# ridicideskaV2.net
KiCad netlist of a schematic drawn in EAGLE
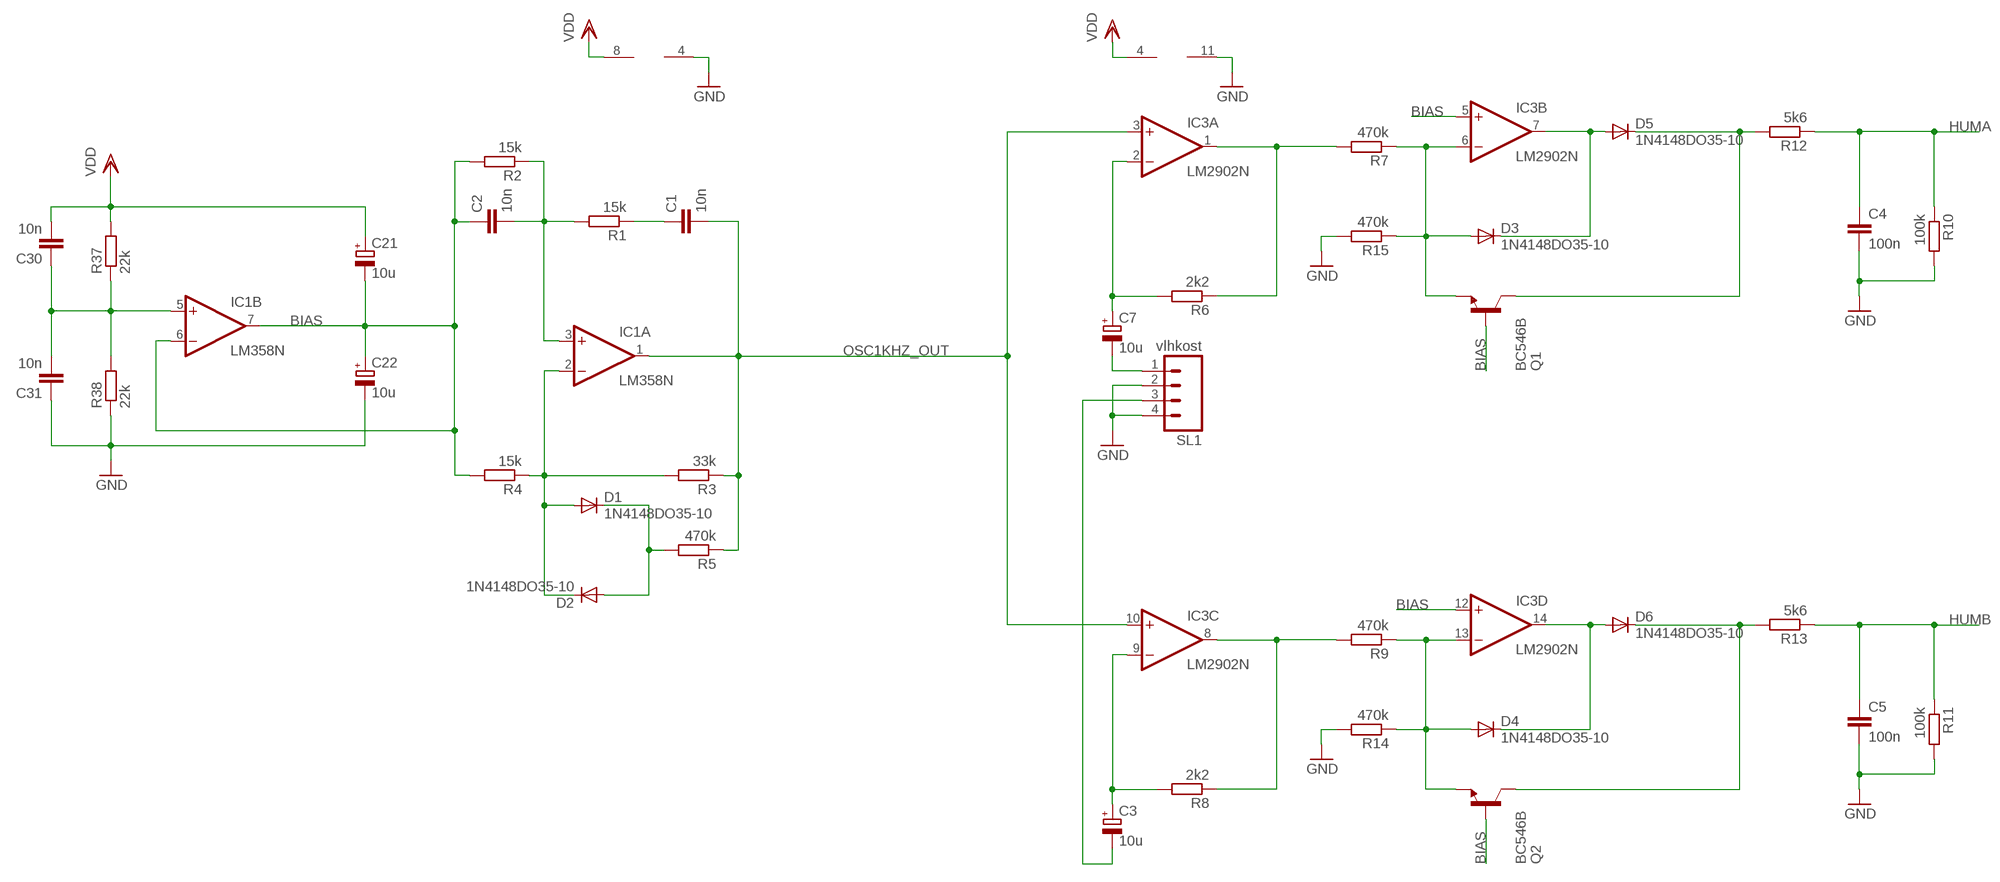
[diagram p0: schematic, sheet 1]
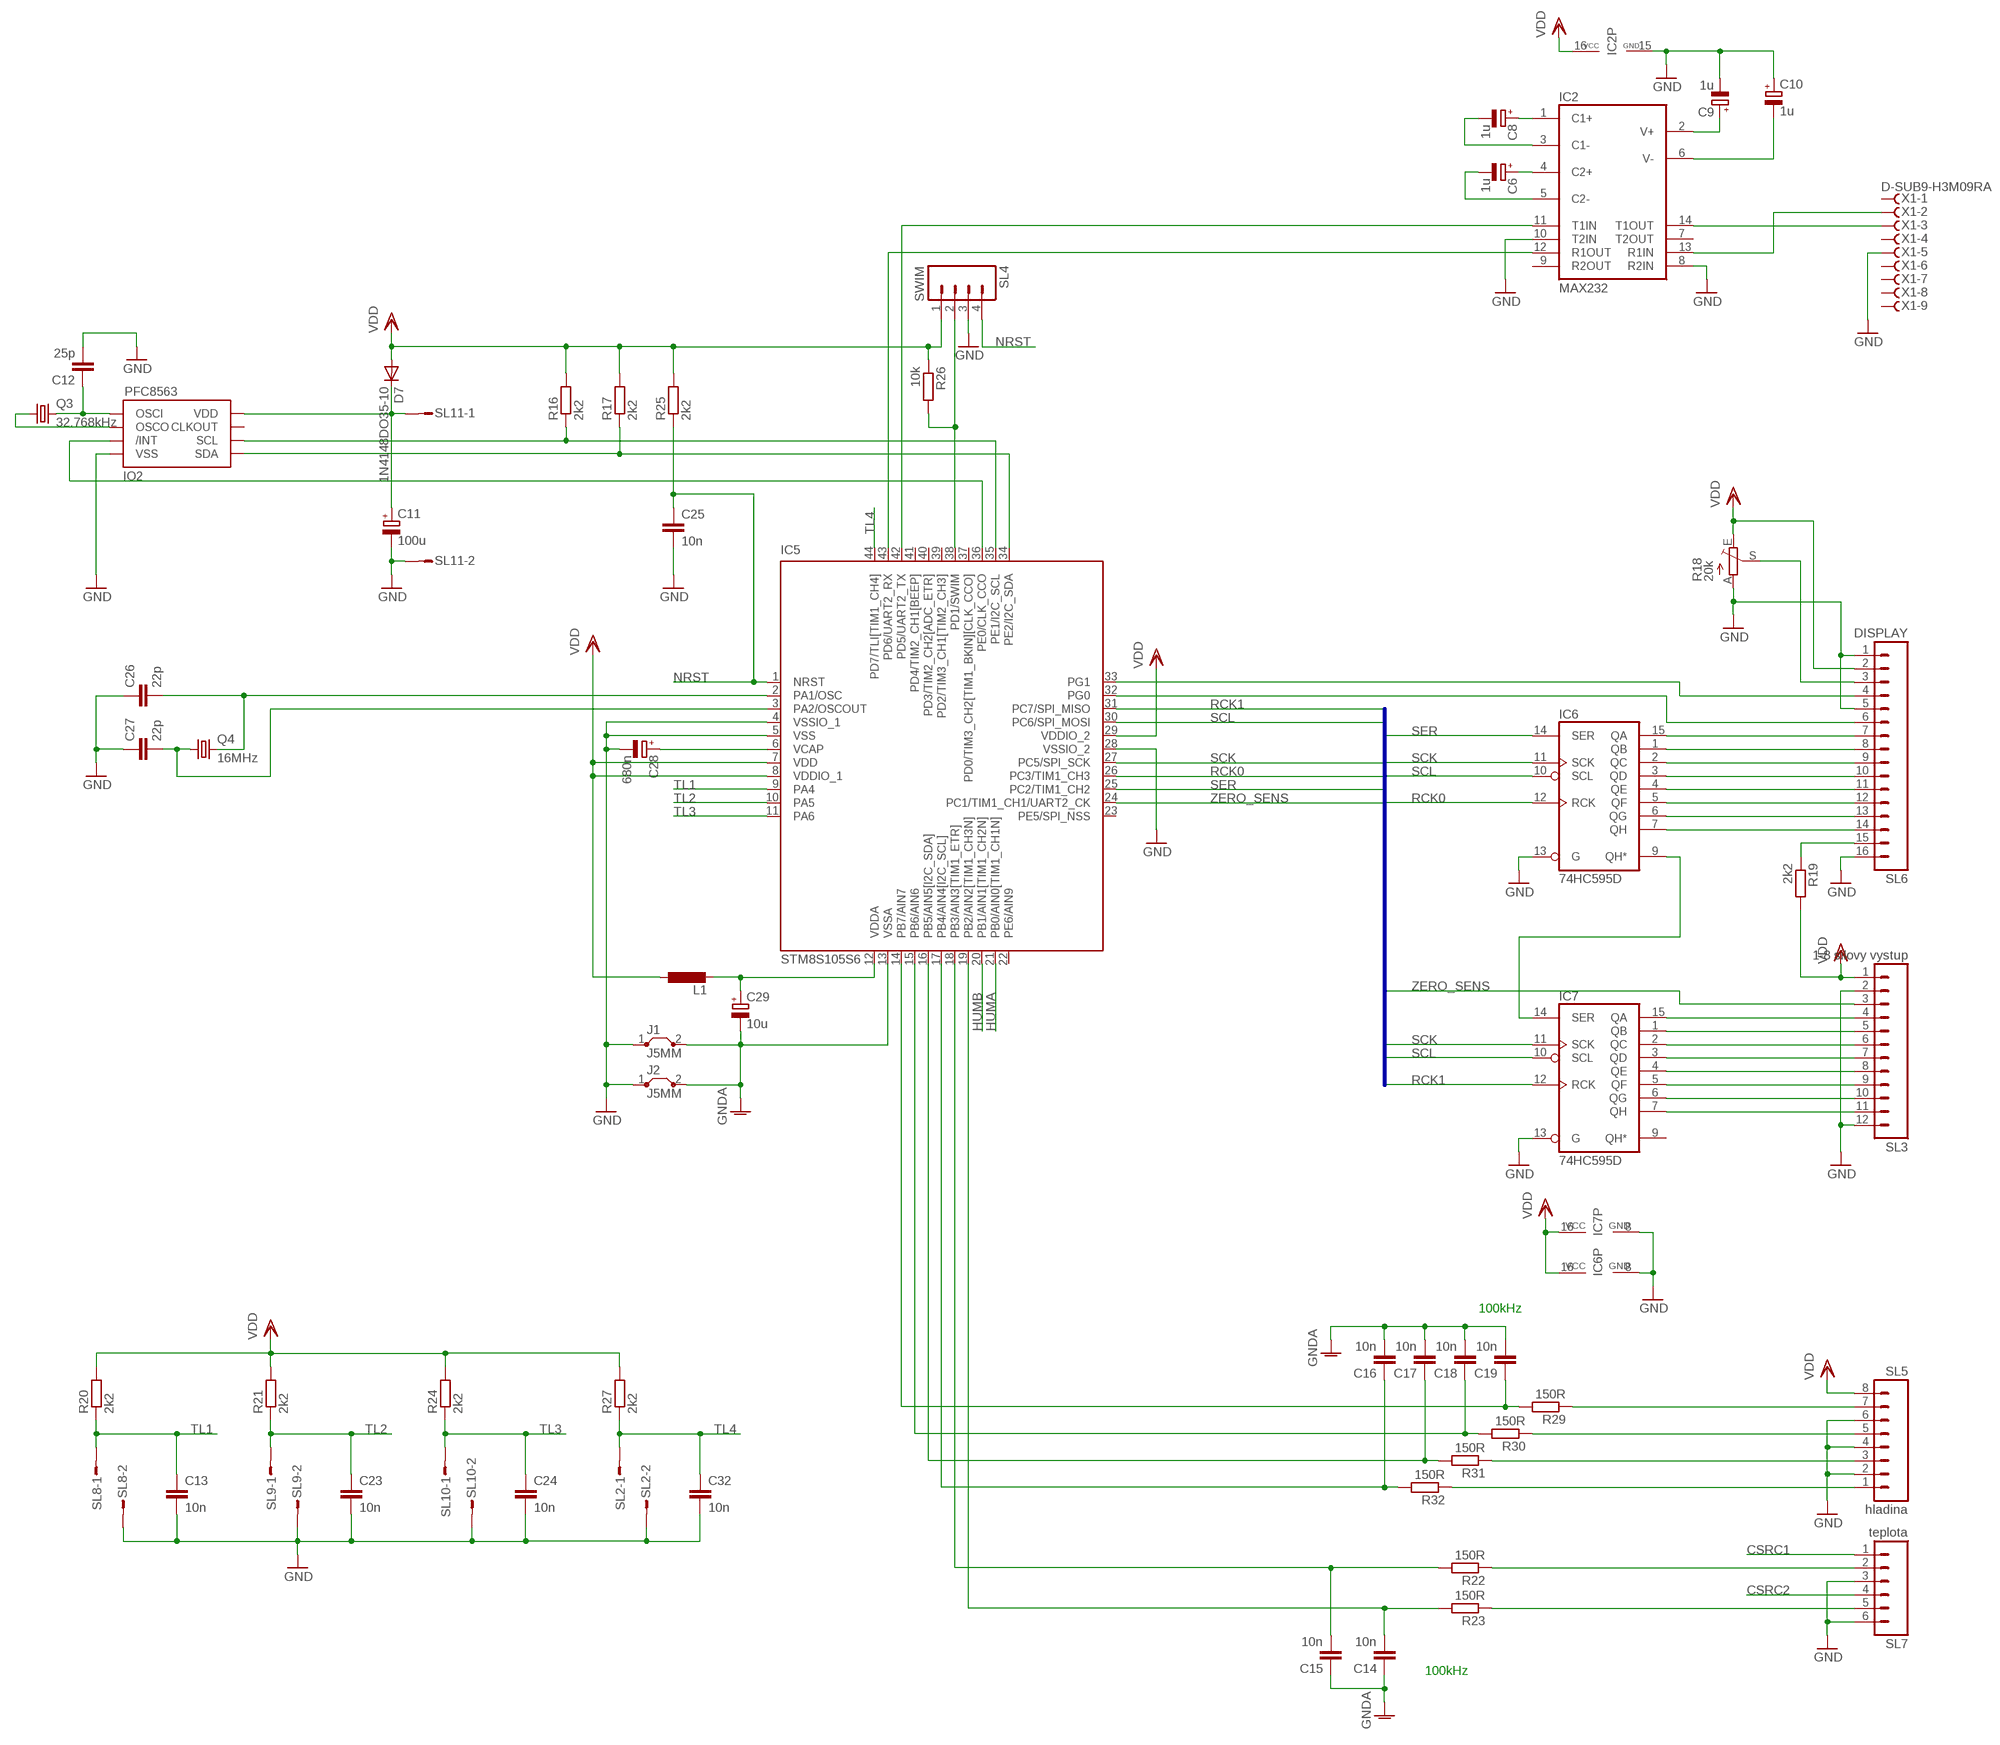
[diagram p1: schematic, sheet 2]
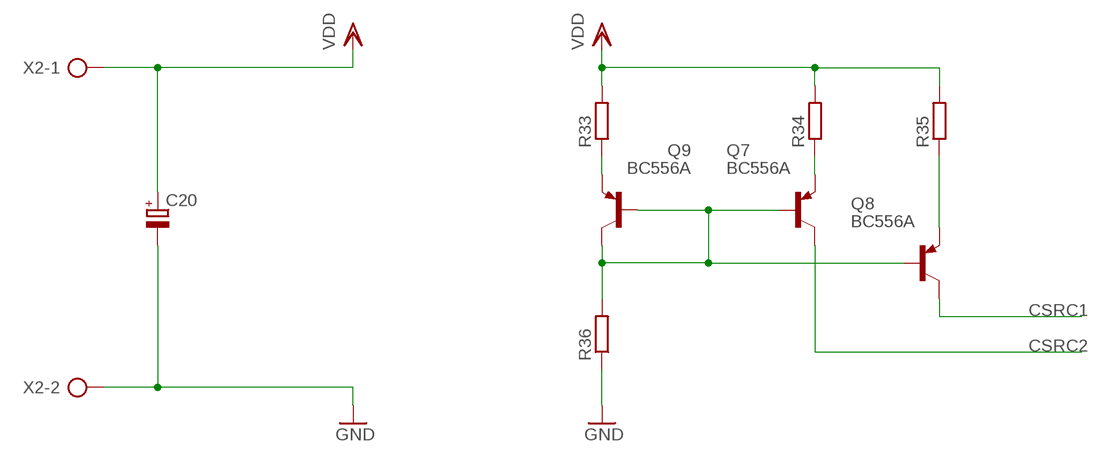
[diagram p2: schematic, sheet 3]

(export (version "E")
  (design (tool "Eeschema 10.0.6"))
  (components
    (comp (ref "C20")
      (value "CPOL-EUE5-10.5")
      (footprint "eagle-import:E5-10,5")
      (libsource (lib "eagle-import") (part "resistor_CPOL-EUE5-10.5"))
    )
    (comp (ref "Q7")
      (value "BC556A")
      (footprint "eagle-import:TO92-EBC")
      (libsource (lib "eagle-import") (part "BC556A"))
    )
    (comp (ref "Q8")
      (value "BC556A")
      (footprint "eagle-import:TO92-EBC")
      (libsource (lib "eagle-import") (part "BC556A"))
    )
    (comp (ref "Q9")
      (value "BC556A")
      (footprint "eagle-import:TO92-EBC")
      (libsource (lib "eagle-import") (part "BC556A"))
    )
    (comp (ref "R33")
      (value "R-EU_R0805")
      (footprint "eagle-import:R0805")
      (libsource (lib "eagle-import") (part "R-EU_R0805"))
    )
    (comp (ref "R34")
      (value "R-EU_R0805")
      (footprint "eagle-import:R0805")
      (libsource (lib "eagle-import") (part "R-EU_R0805"))
    )
    (comp (ref "R35")
      (value "R-EU_R0805")
      (footprint "eagle-import:R0805")
      (libsource (lib "eagle-import") (part "R-EU_R0805"))
    )
    (comp (ref "R36")
      (value "R-EU_R0805")
      (footprint "eagle-import:R0805")
      (libsource (lib "eagle-import") (part "R-EU_R0805"))
    )
    (comp (ref "X2")
      (value "AK300/2")
      (footprint "eagle-import:AK300_2")
      (libsource (lib "eagle-import") (part "AK300/2"))
    )
    (comp (ref "C6")
      (value "1u")
      (footprint "eagle-import:E3,5-8")
      (libsource (lib "eagle-import") (part "resistor_CPOL-EUE3.5-8"))
    )
    (comp (ref "C8")
      (value "1u")
      (footprint "eagle-import:E3,5-8")
      (libsource (lib "eagle-import") (part "resistor_CPOL-EUE3.5-8"))
    )
    (comp (ref "C9")
      (value "1u")
      (footprint "eagle-import:E3,5-8")
      (libsource (lib "eagle-import") (part "resistor_CPOL-EUE3.5-8"))
    )
    (comp (ref "C10")
      (value "1u")
      (footprint "eagle-import:E3,5-8")
      (libsource (lib "eagle-import") (part "resistor_CPOL-EUE3.5-8"))
    )
    (comp (ref "C11")
      (value "100u")
      (footprint "eagle-import:E5-10,5")
      (libsource (lib "eagle-import") (part "resistor_CPOL-EUE5-10.5"))
    )
    (comp (ref "C12")
      (value "25p")
      (footprint "eagle-import:C0805")
      (libsource (lib "eagle-import") (part "C-EUC0805"))
    )
    (comp (ref "C13")
      (value "10n")
      (footprint "eagle-import:C0805")
      (libsource (lib "eagle-import") (part "C-EUC0805"))
    )
    (comp (ref "C14")
      (value "10n")
      (footprint "eagle-import:C0805")
      (libsource (lib "eagle-import") (part "C-EUC0805"))
    )
    (comp (ref "C15")
      (value "10n")
      (footprint "eagle-import:C0805")
      (libsource (lib "eagle-import") (part "C-EUC0805"))
    )
    (comp (ref "C16")
      (value "10n")
      (footprint "eagle-import:C0805")
      (libsource (lib "eagle-import") (part "C-EUC0805"))
    )
    (comp (ref "C17")
      (value "10n")
      (footprint "eagle-import:C0805")
      (libsource (lib "eagle-import") (part "C-EUC0805"))
    )
    (comp (ref "C18")
      (value "10n")
      (footprint "eagle-import:C0805")
      (libsource (lib "eagle-import") (part "C-EUC0805"))
    )
    (comp (ref "C19")
      (value "10n")
      (footprint "eagle-import:C0805")
      (libsource (lib "eagle-import") (part "C-EUC0805"))
    )
    (comp (ref "C23")
      (value "10n")
      (footprint "eagle-import:C0805")
      (libsource (lib "eagle-import") (part "C-EUC0805"))
    )
    (comp (ref "C24")
      (value "10n")
      (footprint "eagle-import:C0805")
      (libsource (lib "eagle-import") (part "C-EUC0805"))
    )
    (comp (ref "C25")
      (value "10n")
      (footprint "eagle-import:C0805")
      (libsource (lib "eagle-import") (part "C-EUC0805"))
    )
    (comp (ref "C26")
      (value "22p")
      (footprint "eagle-import:C0805")
      (libsource (lib "eagle-import") (part "C-EUC0805"))
    )
    (comp (ref "C27")
      (value "22p")
      (footprint "eagle-import:C0805")
      (libsource (lib "eagle-import") (part "C-EUC0805"))
    )
    (comp (ref "C28")
      (value "680n")
      (footprint "eagle-import:SMC_B")
      (libsource (lib "eagle-import") (part "CPOL-EUSMCB"))
    )
    (comp (ref "C29")
      (value "10u")
      (footprint "eagle-import:E5-10,5")
      (libsource (lib "eagle-import") (part "resistor_CPOL-EUE5-10.5"))
    )
    (comp (ref "C32")
      (value "10n")
      (footprint "eagle-import:C0805")
      (libsource (lib "eagle-import") (part "C-EUC0805"))
    )
    (comp (ref "D7")
      (value "1N4148DO35-10")
      (footprint "eagle-import:DO35-10")
      (libsource (lib "eagle-import") (part "1N4148DO35-10"))
    )
    (comp (ref "IC2")
      (value "MAX232")
      (footprint "eagle-import:DIL16")
      (fields (field (name "MF") "MAXIM") (field (name "MPN") "MAX232ACPE+"))
      (libsource (lib "eagle-import") (part "MAX232"))
    )
    (comp (ref "IC5")
      (value "STM8S105S6")
      (footprint "eagle-import:LQFP44-10X10")
      (fields (field (name "MPN") "STM8S105S6T6C"))
      (libsource (lib "eagle-import") (part "STM8S105S6"))
    )
    (comp (ref "IC6")
      (value "74HC595D")
      (footprint "eagle-import:SO16")
      (libsource (lib "eagle-import") (part "74595DHC"))
    )
    (comp (ref "IC7")
      (value "74HC595D")
      (footprint "eagle-import:SO16")
      (libsource (lib "eagle-import") (part "74595DHC"))
    )
    (comp (ref "IO2")
      (value "PFC8563")
      (footprint "eagle-import:SO08")
      (libsource (lib "eagle-import") (part "PFC8563"))
    )
    (comp (ref "J1")
      (value "J5MM")
      (footprint "eagle-import:05")
      (libsource (lib "eagle-import") (part "J5MM"))
    )
    (comp (ref "J2")
      (value "J5MM")
      (footprint "eagle-import:05")
      (libsource (lib "eagle-import") (part "J5MM"))
    )
    (comp (ref "L1")
      (value "L-EU0207/12")
      (footprint "eagle-import:0207_12")
      (libsource (lib "eagle-import") (part "L-EU0207/12"))
    )
    (comp (ref "Q3")
      (value "32.768kHz")
      (footprint "eagle-import:HC49U70")
      (libsource (lib "eagle-import") (part "CRYSTALHC49U70"))
    )
    (comp (ref "Q4")
      (value "16MHz")
      (footprint "eagle-import:HC49U-V")
      (libsource (lib "eagle-import") (part "CRYSTALHC49U-V"))
    )
    (comp (ref "R16")
      (value "2k2")
      (footprint "eagle-import:0207_12@1")
      (libsource (lib "eagle-import") (part "R-EU_0207/12"))
    )
    (comp (ref "R17")
      (value "2k2")
      (footprint "eagle-import:0207_12@1")
      (libsource (lib "eagle-import") (part "R-EU_0207/12"))
    )
    (comp (ref "R18")
      (value "20k")
      (footprint "eagle-import:CA6V")
      (libsource (lib "eagle-import") (part "TRIM_EU-CA6V"))
    )
    (comp (ref "R19")
      (value "2k2")
      (footprint "eagle-import:0207_12@1")
      (libsource (lib "eagle-import") (part "R-EU_0207/12"))
    )
    (comp (ref "R20")
      (value "2k2")
      (footprint "eagle-import:0207_12@1")
      (libsource (lib "eagle-import") (part "R-EU_0207/12"))
    )
    (comp (ref "R21")
      (value "2k2")
      (footprint "eagle-import:0207_12@1")
      (libsource (lib "eagle-import") (part "R-EU_0207/12"))
    )
    (comp (ref "R22")
      (value "150R")
      (footprint "eagle-import:R0805")
      (libsource (lib "eagle-import") (part "R-EU_R0805"))
    )
    (comp (ref "R23")
      (value "150R")
      (footprint "eagle-import:R0805")
      (libsource (lib "eagle-import") (part "R-EU_R0805"))
    )
    (comp (ref "R24")
      (value "2k2")
      (footprint "eagle-import:0207_12@1")
      (libsource (lib "eagle-import") (part "R-EU_0207/12"))
    )
    (comp (ref "R25")
      (value "2k2")
      (footprint "eagle-import:0207_12@1")
      (libsource (lib "eagle-import") (part "R-EU_0207/12"))
    )
    (comp (ref "R26")
      (value "10k")
      (footprint "eagle-import:R0805")
      (libsource (lib "eagle-import") (part "R-EU_R0805"))
    )
    (comp (ref "R27")
      (value "2k2")
      (footprint "eagle-import:0207_12@1")
      (libsource (lib "eagle-import") (part "R-EU_0207/12"))
    )
    (comp (ref "R29")
      (value "150R")
      (footprint "eagle-import:R0805")
      (libsource (lib "eagle-import") (part "R-EU_R0805"))
    )
    (comp (ref "R30")
      (value "150R")
      (footprint "eagle-import:R0805")
      (libsource (lib "eagle-import") (part "R-EU_R0805"))
    )
    (comp (ref "R31")
      (value "150R")
      (footprint "eagle-import:R0805")
      (libsource (lib "eagle-import") (part "R-EU_R0805"))
    )
    (comp (ref "R32")
      (value "150R")
      (footprint "eagle-import:R0805")
      (libsource (lib "eagle-import") (part "R-EU_R0805"))
    )
    (comp (ref "SL2")
      (value "M02S")
      (footprint "eagle-import:02P")
      (libsource (lib "eagle-import") (part "M02S"))
    )
    (comp (ref "SL3")
      (value "1-8 silovy vystup")
      (footprint "eagle-import:12P")
      (libsource (lib "eagle-import") (part "M12"))
    )
    (comp (ref "SL4")
      (value "SWIM")
      (footprint "eagle-import:04P")
      (libsource (lib "eagle-import") (part "M04"))
    )
    (comp (ref "SL5")
      (value "hladina")
      (footprint "eagle-import:08P")
      (fields (field (name "OC_FARNELL") "unknown") (field (name "OC_NEWARK") "unknown"))
      (libsource (lib "eagle-import") (part "M08"))
    )
    (comp (ref "SL6")
      (value "DISPLAY")
      (footprint "eagle-import:16P")
      (libsource (lib "eagle-import") (part "M16"))
    )
    (comp (ref "SL7")
      (value "teplota")
      (footprint "eagle-import:06P")
      (libsource (lib "eagle-import") (part "M06"))
    )
    (comp (ref "SL8")
      (value "M02S")
      (footprint "eagle-import:02P")
      (libsource (lib "eagle-import") (part "M02S"))
    )
    (comp (ref "SL9")
      (value "M02S")
      (footprint "eagle-import:02P")
      (libsource (lib "eagle-import") (part "M02S"))
    )
    (comp (ref "SL10")
      (value "M02S")
      (footprint "eagle-import:02P")
      (libsource (lib "eagle-import") (part "M02S"))
    )
    (comp (ref "SL11")
      (value "M02S")
      (footprint "eagle-import:02P")
      (libsource (lib "eagle-import") (part "M02S"))
    )
    (comp (ref "X1")
      (value "D-SUB9-H3M09RA")
      (footprint "eagle-import:H3M09RA")
      (libsource (lib "eagle-import") (part "D-SUB9-H3M09RA"))
    )
    (comp (ref "C1")
      (value "10n")
      (footprint "eagle-import:C0805")
      (libsource (lib "eagle-import") (part "C-EUC0805"))
    )
    (comp (ref "C2")
      (value "10n")
      (footprint "eagle-import:C0805")
      (libsource (lib "eagle-import") (part "C-EUC0805"))
    )
    (comp (ref "C3")
      (value "10u")
      (footprint "eagle-import:E3,5-8")
      (libsource (lib "eagle-import") (part "CPOL-EUE3.5-8"))
    )
    (comp (ref "C4")
      (value "100n")
      (footprint "eagle-import:C0805")
      (libsource (lib "eagle-import") (part "C-EUC0805"))
    )
    (comp (ref "C5")
      (value "100n")
      (footprint "eagle-import:C0805")
      (libsource (lib "eagle-import") (part "C-EUC0805"))
    )
    (comp (ref "C7")
      (value "10u")
      (footprint "eagle-import:E3,5-8")
      (libsource (lib "eagle-import") (part "CPOL-EUE3.5-8"))
    )
    (comp (ref "C21")
      (value "10u")
      (footprint "eagle-import:E3,5-8")
      (libsource (lib "eagle-import") (part "resistor_CPOL-EUE3.5-8"))
    )
    (comp (ref "C22")
      (value "10u")
      (footprint "eagle-import:E3,5-8")
      (libsource (lib "eagle-import") (part "resistor_CPOL-EUE3.5-8"))
    )
    (comp (ref "C30")
      (value "10n")
      (footprint "eagle-import:C0805")
      (libsource (lib "eagle-import") (part "C-EUC0805"))
    )
    (comp (ref "C31")
      (value "10n")
      (footprint "eagle-import:C0805")
      (libsource (lib "eagle-import") (part "C-EUC0805"))
    )
    (comp (ref "D1")
      (value "1N4148DO35-10")
      (footprint "eagle-import:DO35-10")
      (libsource (lib "eagle-import") (part "1N4148DO35-10"))
    )
    (comp (ref "D2")
      (value "1N4148DO35-10")
      (footprint "eagle-import:DO35-10")
      (libsource (lib "eagle-import") (part "1N4148DO35-10"))
    )
    (comp (ref "D3")
      (value "1N4148DO35-10")
      (footprint "eagle-import:DO35-10")
      (libsource (lib "eagle-import") (part "1N4148DO35-10"))
    )
    (comp (ref "D4")
      (value "1N4148DO35-10")
      (footprint "eagle-import:DO35-10")
      (libsource (lib "eagle-import") (part "1N4148DO35-10"))
    )
    (comp (ref "D5")
      (value "1N4148DO35-10")
      (footprint "eagle-import:DO35-10")
      (libsource (lib "eagle-import") (part "1N4148DO35-10"))
    )
    (comp (ref "D6")
      (value "1N4148DO35-10")
      (footprint "eagle-import:DO35-10")
      (libsource (lib "eagle-import") (part "1N4148DO35-10"))
    )
    (comp (ref "IC1")
      (value "LM358N")
      (footprint "eagle-import:DIL08")
      (libsource (lib "eagle-import") (part "LM358N"))
    )
    (comp (ref "IC3")
      (value "LM2902N")
      (footprint "eagle-import:DIL14")
      (libsource (lib "eagle-import") (part "LM2902N"))
    )
    (comp (ref "Q1")
      (value "BC546B")
      (footprint "eagle-import:TO92-EBC")
      (libsource (lib "eagle-import") (part "BC546B"))
    )
    (comp (ref "Q2")
      (value "BC546B")
      (footprint "eagle-import:TO92-EBC")
      (libsource (lib "eagle-import") (part "BC546B"))
    )
    (comp (ref "R1")
      (value "15k")
      (footprint "eagle-import:R0805")
      (libsource (lib "eagle-import") (part "R-EU_R0805"))
    )
    (comp (ref "R2")
      (value "15k")
      (footprint "eagle-import:R0805")
      (libsource (lib "eagle-import") (part "R-EU_R0805"))
    )
    (comp (ref "R3")
      (value "33k")
      (footprint "eagle-import:R0805")
      (libsource (lib "eagle-import") (part "R-EU_R0805"))
    )
    (comp (ref "R4")
      (value "15k")
      (footprint "eagle-import:R0805")
      (libsource (lib "eagle-import") (part "R-EU_R0805"))
    )
    (comp (ref "R5")
      (value "470k")
      (footprint "eagle-import:R0805")
      (libsource (lib "eagle-import") (part "R-EU_R0805"))
    )
    (comp (ref "R6")
      (value "2k2")
      (footprint "eagle-import:R0805")
      (libsource (lib "eagle-import") (part "R-EU_R0805"))
    )
    (comp (ref "R7")
      (value "470k")
      (footprint "eagle-import:R0805")
      (libsource (lib "eagle-import") (part "R-EU_R0805"))
    )
    (comp (ref "R8")
      (value "2k2")
      (footprint "eagle-import:R0805")
      (libsource (lib "eagle-import") (part "R-EU_R0805"))
    )
    (comp (ref "R9")
      (value "470k")
      (footprint "eagle-import:R0805")
      (libsource (lib "eagle-import") (part "R-EU_R0805"))
    )
    (comp (ref "R10")
      (value "100k")
      (footprint "eagle-import:R0805")
      (libsource (lib "eagle-import") (part "R-EU_R0805"))
    )
    (comp (ref "R11")
      (value "100k")
      (footprint "eagle-import:R0805")
      (libsource (lib "eagle-import") (part "R-EU_R0805"))
    )
    (comp (ref "R12")
      (value "5k6")
      (footprint "eagle-import:R0805")
      (libsource (lib "eagle-import") (part "R-EU_R0805"))
    )
    (comp (ref "R13")
      (value "5k6")
      (footprint "eagle-import:R0805")
      (libsource (lib "eagle-import") (part "R-EU_R0805"))
    )
    (comp (ref "R14")
      (value "470k")
      (footprint "eagle-import:R0805")
      (libsource (lib "eagle-import") (part "R-EU_R0805"))
    )
    (comp (ref "R15")
      (value "470k")
      (footprint "eagle-import:R0805")
      (libsource (lib "eagle-import") (part "R-EU_R0805"))
    )
    (comp (ref "R37")
      (value "22k")
      (footprint "eagle-import:0207_12")
      (libsource (lib "eagle-import") (part "resistor_R-EU_0207/12"))
    )
    (comp (ref "R38")
      (value "22k")
      (footprint "eagle-import:0207_12")
      (libsource (lib "eagle-import") (part "resistor_R-EU_0207/12"))
    )
    (comp (ref "SL1")
      (value "vlhkost")
      (footprint "eagle-import:04P")
      (libsource (lib "eagle-import") (part "M04"))
    )
  )
  (nets
    (net (code "1") (name "BIAS") (class "Default")
      (node (ref "C2") (pin "1") (pinfunction "1_1") (pintype "passive"))
      (node (ref "C21") (pin "-") (pinfunction "-_-") (pintype "passive"))
      (node (ref "C22") (pin "+") (pinfunction "+_+") (pintype "passive"))
      (node (ref "IC1") (pin "6") (pinfunction "-IN_6") (pintype "input"))
      (node (ref "IC1") (pin "7") (pinfunction "OUT_7") (pintype "output"))
      (node (ref "IC3") (pin "12") (pinfunction "+IN_12") (pintype "input"))
      (node (ref "IC3") (pin "5") (pinfunction "+IN_5") (pintype "input"))
      (node (ref "Q1") (pin "B") (pinfunction "B_B") (pintype "passive"))
      (node (ref "Q2") (pin "B") (pinfunction "B_B") (pintype "passive"))
      (node (ref "R2") (pin "2") (pinfunction "2_2") (pintype "passive"))
      (node (ref "R4") (pin "2") (pinfunction "2_2") (pintype "passive"))
    )
    (net (code "2") (name "CSRC1") (class "Default")
      (node (ref "Q8") (pin "C") (pinfunction "C_C") (pintype "passive"))
      (node (ref "SL7") (pin "1") (pinfunction "1_1") (pintype "passive"))
    )
    (net (code "3") (name "CSRC2") (class "Default")
      (node (ref "Q7") (pin "C") (pinfunction "C_C") (pintype "passive"))
      (node (ref "SL7") (pin "4") (pinfunction "4_4") (pintype "passive"))
    )
    (net (code "4") (name "GND") (class "Default")
      (node (ref "C10") (pin "+") (pinfunction "+_+") (pintype "passive"))
      (node (ref "C11") (pin "-") (pinfunction "-_-") (pintype "passive"))
      (node (ref "C12") (pin "2") (pinfunction "2_2") (pintype "passive"))
      (node (ref "C13") (pin "2") (pinfunction "2_2") (pintype "passive"))
      (node (ref "C20") (pin "-") (pinfunction "-_-") (pintype "passive"))
      (node (ref "C22") (pin "-") (pinfunction "-_-") (pintype "passive"))
      (node (ref "C23") (pin "2") (pinfunction "2_2") (pintype "passive"))
      (node (ref "C24") (pin "2") (pinfunction "2_2") (pintype "passive"))
      (node (ref "C25") (pin "2") (pinfunction "2_2") (pintype "passive"))
      (node (ref "C26") (pin "1") (pinfunction "1_1") (pintype "passive"))
      (node (ref "C27") (pin "1") (pinfunction "1_1") (pintype "passive"))
      (node (ref "C28") (pin "-") (pinfunction "-_-") (pintype "passive"))
      (node (ref "C31") (pin "1") (pinfunction "1_1") (pintype "passive"))
      (node (ref "C32") (pin "2") (pinfunction "2_2") (pintype "passive"))
      (node (ref "C4") (pin "2") (pinfunction "2_2") (pintype "passive"))
      (node (ref "C5") (pin "2") (pinfunction "2_2") (pintype "passive"))
      (node (ref "C9") (pin "-") (pinfunction "-_-") (pintype "passive"))
      (node (ref "IC1") (pin "4") (pinfunction "V-_4") (pintype "power_in"))
      (node (ref "IC2") (pin "10") (pinfunction "T2IN_10") (pintype "input"))
      (node (ref "IC2") (pin "15") (pinfunction "GND_15") (pintype "power_in"))
      (node (ref "IC2") (pin "8") (pinfunction "R2IN_8") (pintype "input"))
      (node (ref "IC3") (pin "11") (pinfunction "V-_11") (pintype "power_in"))
      (node (ref "IC5") (pin "28") (pinfunction "VSSIO_2_28") (pintype "power_in"))
      (node (ref "IC5") (pin "4") (pinfunction "VSSIO_1_4") (pintype "power_in"))
      (node (ref "IC5") (pin "5") (pinfunction "VSS_5") (pintype "power_in"))
      (node (ref "IC6") (pin "13") (pinfunction "G_13") (pintype "input"))
      (node (ref "IC6") (pin "8") (pinfunction "GND_8") (pintype "power_in"))
      (node (ref "IC7") (pin "13") (pinfunction "G_13") (pintype "input"))
      (node (ref "IC7") (pin "8") (pinfunction "GND_8") (pintype "power_in"))
      (node (ref "IO2") (pin "4") (pinfunction "VSS_4") (pintype "bidirectional"))
      (node (ref "J1") (pin "1") (pinfunction "1_1") (pintype "passive"))
      (node (ref "J2") (pin "1") (pinfunction "1_1") (pintype "passive"))
      (node (ref "R10") (pin "2") (pinfunction "2_2") (pintype "passive"))
      (node (ref "R11") (pin "2") (pinfunction "2_2") (pintype "passive"))
      (node (ref "R14") (pin "2") (pinfunction "2_2") (pintype "passive"))
      (node (ref "R15") (pin "2") (pinfunction "2_2") (pintype "passive"))
      (node (ref "R18") (pin "A") (pinfunction "A_A") (pintype "passive"))
      (node (ref "R36") (pin "1") (pinfunction "1_1") (pintype "passive"))
      (node (ref "R38") (pin "1") (pinfunction "1_1") (pintype "passive"))
      (node (ref "SL1") (pin "2") (pinfunction "2_2") (pintype "passive"))
      (node (ref "SL1") (pin "4") (pinfunction "4_4") (pintype "passive"))
      (node (ref "SL10") (pin "2") (pinfunction "S_2") (pintype "passive"))
      (node (ref "SL11") (pin "2") (pinfunction "S_2") (pintype "passive"))
      (node (ref "SL2") (pin "2") (pinfunction "S_2") (pintype "passive"))
      (node (ref "SL3") (pin "12") (pinfunction "12_12") (pintype "passive"))
      (node (ref "SL3") (pin "2") (pinfunction "2_2") (pintype "passive"))
      (node (ref "SL4") (pin "3") (pinfunction "3_3") (pintype "passive"))
      (node (ref "SL5") (pin "2") (pinfunction "2_2") (pintype "passive"))
      (node (ref "SL5") (pin "4") (pinfunction "4_4") (pintype "passive"))
      (node (ref "SL5") (pin "6") (pinfunction "6_6") (pintype "passive"))
      (node (ref "SL6") (pin "1") (pinfunction "1_1") (pintype "passive"))
      (node (ref "SL6") (pin "16") (pinfunction "16_16") (pintype "passive"))
      (node (ref "SL6") (pin "5") (pinfunction "5_5") (pintype "passive"))
      (node (ref "SL7") (pin "3") (pinfunction "3_3") (pintype "passive"))
      (node (ref "SL7") (pin "6") (pinfunction "6_6") (pintype "passive"))
      (node (ref "SL8") (pin "2") (pinfunction "S_2") (pintype "passive"))
      (node (ref "SL9") (pin "2") (pinfunction "S_2") (pintype "passive"))
      (node (ref "X1") (pin "5") (pinfunction "F_5") (pintype "passive"))
      (node (ref "X2") (pin "2") (pinfunction "KL_2") (pintype "passive"))
    )
    (net (code "5") (name "GNDA") (class "Default")
      (node (ref "C14") (pin "1") (pinfunction "1_1") (pintype "passive"))
      (node (ref "C15") (pin "1") (pinfunction "1_1") (pintype "passive"))
      (node (ref "C16") (pin "2") (pinfunction "2_2") (pintype "passive"))
      (node (ref "C17") (pin "2") (pinfunction "2_2") (pintype "passive"))
      (node (ref "C18") (pin "2") (pinfunction "2_2") (pintype "passive"))
      (node (ref "C19") (pin "2") (pinfunction "2_2") (pintype "passive"))
      (node (ref "C29") (pin "-") (pinfunction "-_-") (pintype "passive"))
      (node (ref "IC5") (pin "13") (pinfunction "VSSA_13") (pintype "power_in"))
      (node (ref "J1") (pin "2") (pinfunction "2_2") (pintype "passive"))
      (node (ref "J2") (pin "2") (pinfunction "2_2") (pintype "passive"))
    )
    (net (code "6") (name "HUMA") (class "Default")
      (node (ref "C4") (pin "1") (pinfunction "1_1") (pintype "passive"))
      (node (ref "IC5") (pin "21") (pinfunction "PB0/AIN0[TIM1_CH1N]_21") (pintype "bidirectional"))
      (node (ref "R10") (pin "1") (pinfunction "1_1") (pintype "passive"))
      (node (ref "R12") (pin "1") (pinfunction "1_1") (pintype "passive"))
    )
    (net (code "7") (name "HUMB") (class "Default")
      (node (ref "C5") (pin "1") (pinfunction "1_1") (pintype "passive"))
      (node (ref "IC5") (pin "20") (pinfunction "PB1/AIN1[TIM1_CH2N]_20") (pintype "bidirectional"))
      (node (ref "R11") (pin "1") (pinfunction "1_1") (pintype "passive"))
      (node (ref "R13") (pin "1") (pinfunction "1_1") (pintype "passive"))
    )
    (net (code "8") (name "NRST") (class "Default")
      (node (ref "C25") (pin "1") (pinfunction "1_1") (pintype "passive"))
      (node (ref "IC5") (pin "1") (pinfunction "NRST_1") (pintype "bidirectional"))
      (node (ref "R25") (pin "1") (pinfunction "1_1") (pintype "passive"))
      (node (ref "SL4") (pin "4") (pinfunction "4_4") (pintype "passive"))
    )
    (net (code "9") (name "Net-(C1-Pad1)") (class "Default")
      (node (ref "C1") (pin "1") (pinfunction "1_1") (pintype "passive"))
      (node (ref "R1") (pin "1") (pinfunction "1_1") (pintype "passive"))
    )
    (net (code "10") (name "Net-(C3-Pad-)") (class "Default")
      (node (ref "C3") (pin "-") (pinfunction "-_-") (pintype "passive"))
      (node (ref "SL1") (pin "3") (pinfunction "3_3") (pintype "passive"))
    )
    (net (code "11") (name "Net-(C7-Pad-)") (class "Default")
      (node (ref "C7") (pin "-") (pinfunction "-_-") (pintype "passive"))
      (node (ref "SL1") (pin "1") (pinfunction "1_1") (pintype "passive"))
    )
    (net (code "12") (name "Net-(D1-PadC)") (class "Default")
      (node (ref "D1") (pin "C") (pinfunction "C_C") (pintype "passive"))
      (node (ref "D2") (pin "A") (pinfunction "A_A") (pintype "passive"))
      (node (ref "R5") (pin "2") (pinfunction "2_2") (pintype "passive"))
    )
    (net (code "13") (name "Net-(D5-PadC)") (class "Default")
      (node (ref "D5") (pin "C") (pinfunction "C_C") (pintype "passive"))
      (node (ref "Q1") (pin "C") (pinfunction "C_C") (pintype "passive"))
      (node (ref "R12") (pin "2") (pinfunction "2_2") (pintype "passive"))
    )
    (net (code "14") (name "Net-(D6-PadC)") (class "Default")
      (node (ref "D6") (pin "C") (pinfunction "C_C") (pintype "passive"))
      (node (ref "Q2") (pin "C") (pinfunction "C_C") (pintype "passive"))
      (node (ref "R13") (pin "2") (pinfunction "2_2") (pintype "passive"))
    )
    (net (code "15") (name "Net-(IC1A-+IN)") (class "Default")
      (node (ref "C2") (pin "2") (pinfunction "2_2") (pintype "passive"))
      (node (ref "IC1") (pin "3") (pinfunction "+IN_3") (pintype "input"))
      (node (ref "R1") (pin "2") (pinfunction "2_2") (pintype "passive"))
      (node (ref "R2") (pin "1") (pinfunction "1_1") (pintype "passive"))
    )
    (net (code "16") (name "Net-(IC1A--IN)") (class "Default")
      (node (ref "D1") (pin "A") (pinfunction "A_A") (pintype "passive"))
      (node (ref "D2") (pin "C") (pinfunction "C_C") (pintype "passive"))
      (node (ref "IC1") (pin "2") (pinfunction "-IN_2") (pintype "input"))
      (node (ref "R3") (pin "2") (pinfunction "2_2") (pintype "passive"))
      (node (ref "R4") (pin "1") (pinfunction "1_1") (pintype "passive"))
    )
    (net (code "17") (name "Net-(IC1B-+IN)") (class "Default")
      (node (ref "C30") (pin "1") (pinfunction "1_1") (pintype "passive"))
      (node (ref "C31") (pin "2") (pinfunction "2_2") (pintype "passive"))
      (node (ref "IC1") (pin "5") (pinfunction "+IN_5") (pintype "input"))
      (node (ref "R37") (pin "1") (pinfunction "1_1") (pintype "passive"))
      (node (ref "R38") (pin "2") (pinfunction "2_2") (pintype "passive"))
    )
    (net (code "18") (name "Net-(IC2A-C1+)") (class "Default")
      (node (ref "C8") (pin "+") (pinfunction "+_+") (pintype "passive"))
      (node (ref "IC2") (pin "1") (pinfunction "C1+_1") (pintype "bidirectional"))
    )
    (net (code "19") (name "Net-(IC2A-C1-)") (class "Default")
      (node (ref "C8") (pin "-") (pinfunction "-_-") (pintype "passive"))
      (node (ref "IC2") (pin "3") (pinfunction "C1-_3") (pintype "bidirectional"))
    )
    (net (code "20") (name "Net-(IC2A-C2+)") (class "Default")
      (node (ref "C6") (pin "+") (pinfunction "+_+") (pintype "passive"))
      (node (ref "IC2") (pin "4") (pinfunction "C2+_4") (pintype "bidirectional"))
    )
    (net (code "21") (name "Net-(IC2A-C2-)") (class "Default")
      (node (ref "C6") (pin "-") (pinfunction "-_-") (pintype "passive"))
      (node (ref "IC2") (pin "5") (pinfunction "C2-_5") (pintype "bidirectional"))
    )
    (net (code "22") (name "Net-(IC2A-R1IN)") (class "Default")
      (node (ref "IC2") (pin "13") (pinfunction "R1IN_13") (pintype "input"))
      (node (ref "X1") (pin "2") (pinfunction "F_2") (pintype "passive"))
    )
    (net (code "23") (name "Net-(IC2A-R1OUT)") (class "Default")
      (node (ref "IC2") (pin "12") (pinfunction "R1OUT_12") (pintype "output"))
      (node (ref "IC5") (pin "43") (pinfunction "PD6/UART2_RX_43") (pintype "bidirectional"))
    )
    (net (code "24") (name "Net-(IC2A-T1IN)") (class "Default")
      (node (ref "IC2") (pin "11") (pinfunction "T1IN_11") (pintype "input"))
      (node (ref "IC5") (pin "42") (pinfunction "PD5/UART2_TX_42") (pintype "bidirectional"))
    )
    (net (code "25") (name "Net-(IC2A-T1OUT)") (class "Default")
      (node (ref "IC2") (pin "14") (pinfunction "T1OUT_14") (pintype "output"))
      (node (ref "X1") (pin "3") (pinfunction "F_3") (pintype "passive"))
    )
    (net (code "26") (name "Net-(IC2A-V+)") (class "Default")
      (node (ref "C9") (pin "+") (pinfunction "+_+") (pintype "passive"))
      (node (ref "IC2") (pin "2") (pinfunction "V+_2") (pintype "bidirectional"))
    )
    (net (code "27") (name "Net-(IC2A-V-)") (class "Default")
      (node (ref "C10") (pin "-") (pinfunction "-_-") (pintype "passive"))
      (node (ref "IC2") (pin "6") (pinfunction "V-_6") (pintype "bidirectional"))
    )
    (net (code "28") (name "Net-(IC3A--IN)") (class "Default")
      (node (ref "C7") (pin "+") (pinfunction "+_+") (pintype "passive"))
      (node (ref "IC3") (pin "2") (pinfunction "-IN_2") (pintype "input"))
      (node (ref "R6") (pin "2") (pinfunction "2_2") (pintype "passive"))
    )
    (net (code "29") (name "Net-(IC3A-OUT)") (class "Default")
      (node (ref "IC3") (pin "1") (pinfunction "OUT_1") (pintype "output"))
      (node (ref "R6") (pin "1") (pinfunction "1_1") (pintype "passive"))
      (node (ref "R7") (pin "2") (pinfunction "2_2") (pintype "passive"))
    )
    (net (code "30") (name "Net-(IC3B--IN)") (class "Default")
      (node (ref "D3") (pin "A") (pinfunction "A_A") (pintype "passive"))
      (node (ref "IC3") (pin "6") (pinfunction "-IN_6") (pintype "input"))
      (node (ref "Q1") (pin "E") (pinfunction "E_E") (pintype "passive"))
      (node (ref "R15") (pin "1") (pinfunction "1_1") (pintype "passive"))
      (node (ref "R7") (pin "1") (pinfunction "1_1") (pintype "passive"))
    )
    (net (code "31") (name "Net-(IC3B-OUT)") (class "Default")
      (node (ref "D3") (pin "C") (pinfunction "C_C") (pintype "passive"))
      (node (ref "D5") (pin "A") (pinfunction "A_A") (pintype "passive"))
      (node (ref "IC3") (pin "7") (pinfunction "OUT_7") (pintype "output"))
    )
    (net (code "32") (name "Net-(IC3C--IN)") (class "Default")
      (node (ref "C3") (pin "+") (pinfunction "+_+") (pintype "passive"))
      (node (ref "IC3") (pin "9") (pinfunction "-IN_9") (pintype "input"))
      (node (ref "R8") (pin "2") (pinfunction "2_2") (pintype "passive"))
    )
    (net (code "33") (name "Net-(IC3C-OUT)") (class "Default")
      (node (ref "IC3") (pin "8") (pinfunction "OUT_8") (pintype "output"))
      (node (ref "R8") (pin "1") (pinfunction "1_1") (pintype "passive"))
      (node (ref "R9") (pin "2") (pinfunction "2_2") (pintype "passive"))
    )
    (net (code "34") (name "Net-(IC3D--IN)") (class "Default")
      (node (ref "D4") (pin "A") (pinfunction "A_A") (pintype "passive"))
      (node (ref "IC3") (pin "13") (pinfunction "-IN_13") (pintype "input"))
      (node (ref "Q2") (pin "E") (pinfunction "E_E") (pintype "passive"))
      (node (ref "R14") (pin "1") (pinfunction "1_1") (pintype "passive"))
      (node (ref "R9") (pin "1") (pinfunction "1_1") (pintype "passive"))
    )
    (net (code "35") (name "Net-(IC3D-OUT)") (class "Default")
      (node (ref "D4") (pin "C") (pinfunction "C_C") (pintype "passive"))
      (node (ref "D6") (pin "A") (pinfunction "A_A") (pintype "passive"))
      (node (ref "IC3") (pin "14") (pinfunction "OUT_14") (pintype "output"))
    )
    (net (code "36") (name "Net-(IC5-PA1{slash}OSC)") (class "Default")
      (node (ref "C26") (pin "2") (pinfunction "2_2") (pintype "passive"))
      (node (ref "IC5") (pin "2") (pinfunction "PA1/OSC_2") (pintype "bidirectional"))
      (node (ref "Q4") (pin "2") (pinfunction "2_2") (pintype "passive"))
    )
    (net (code "37") (name "Net-(IC5-PA2{slash}OSCOUT)") (class "Default")
      (node (ref "C27") (pin "2") (pinfunction "2_2") (pintype "passive"))
      (node (ref "IC5") (pin "3") (pinfunction "PA2/OSCOUT_3") (pintype "bidirectional"))
      (node (ref "Q4") (pin "1") (pinfunction "1_1") (pintype "passive"))
    )
    (net (code "38") (name "Net-(IC5-PB2{slash}AIN2[TIM1_CH3N])") (class "Default")
      (node (ref "C14") (pin "2") (pinfunction "2_2") (pintype "passive"))
      (node (ref "IC5") (pin "19") (pinfunction "PB2/AIN2[TIM1_CH3N]_19") (pintype "bidirectional"))
      (node (ref "R23") (pin "2") (pinfunction "2_2") (pintype "passive"))
    )
    (net (code "39") (name "Net-(IC5-PB3{slash}AIN3[TIM1_ETR])") (class "Default")
      (node (ref "C15") (pin "2") (pinfunction "2_2") (pintype "passive"))
      (node (ref "IC5") (pin "18") (pinfunction "PB3/AIN3[TIM1_ETR]_18") (pintype "bidirectional"))
      (node (ref "R22") (pin "2") (pinfunction "2_2") (pintype "passive"))
    )
    (net (code "40") (name "Net-(IC5-PB4{slash}AIN4[I2C_SCL])") (class "Default")
      (node (ref "C16") (pin "1") (pinfunction "1_1") (pintype "passive"))
      (node (ref "IC5") (pin "17") (pinfunction "PB4/AIN4[I2C_SCL]_17") (pintype "bidirectional"))
      (node (ref "R32") (pin "2") (pinfunction "2_2") (pintype "passive"))
    )
    (net (code "41") (name "Net-(IC5-PB5{slash}AIN5[I2C_SDA])") (class "Default")
      (node (ref "C17") (pin "1") (pinfunction "1_1") (pintype "passive"))
      (node (ref "IC5") (pin "16") (pinfunction "PB5/AIN5[I2C_SDA]_16") (pintype "bidirectional"))
      (node (ref "R31") (pin "2") (pinfunction "2_2") (pintype "passive"))
    )
    (net (code "42") (name "Net-(IC5-PB6{slash}AIN6)") (class "Default")
      (node (ref "C18") (pin "1") (pinfunction "1_1") (pintype "passive"))
      (node (ref "IC5") (pin "15") (pinfunction "PB6/AIN6_15") (pintype "bidirectional"))
      (node (ref "R30") (pin "2") (pinfunction "2_2") (pintype "passive"))
    )
    (net (code "43") (name "Net-(IC5-PB7{slash}AIN7)") (class "Default")
      (node (ref "C19") (pin "1") (pinfunction "1_1") (pintype "passive"))
      (node (ref "IC5") (pin "14") (pinfunction "PB7/AIN7_14") (pintype "bidirectional"))
      (node (ref "R29") (pin "2") (pinfunction "2_2") (pintype "passive"))
    )
    (net (code "44") (name "Net-(IC5-PD1{slash}SWIM)") (class "Default")
      (node (ref "IC5") (pin "38") (pinfunction "PD1/SWIM_38") (pintype "bidirectional"))
      (node (ref "R26") (pin "2") (pinfunction "2_2") (pintype "passive"))
      (node (ref "SL4") (pin "2") (pinfunction "2_2") (pintype "passive"))
    )
    (net (code "45") (name "Net-(IC5-PE0{slash}CLK_CCO)") (class "Default")
      (node (ref "IC5") (pin "36") (pinfunction "PE0/CLK_CCO_36") (pintype "bidirectional"))
      (node (ref "IO2") (pin "3") (pinfunction "/INT_3") (pintype "bidirectional"))
    )
    (net (code "46") (name "Net-(IC5-PE1{slash}I2C_SCL)") (class "Default")
      (node (ref "IC5") (pin "35") (pinfunction "PE1/I2C_SCL_35") (pintype "bidirectional"))
      (node (ref "IO2") (pin "6") (pinfunction "SCL_6") (pintype "bidirectional"))
      (node (ref "R16") (pin "1") (pinfunction "1_1") (pintype "passive"))
    )
    (net (code "47") (name "Net-(IC5-PE2{slash}I2C_SDA)") (class "Default")
      (node (ref "IC5") (pin "34") (pinfunction "PE2/I2C_SDA_34") (pintype "bidirectional"))
      (node (ref "IO2") (pin "5") (pinfunction "SDA_5") (pintype "bidirectional"))
      (node (ref "R17") (pin "1") (pinfunction "1_1") (pintype "passive"))
    )
    (net (code "48") (name "Net-(IC5-PG0)") (class "Default")
      (node (ref "IC5") (pin "32") (pinfunction "PG0_32") (pintype "bidirectional"))
      (node (ref "SL6") (pin "6") (pinfunction "6_6") (pintype "passive"))
    )
    (net (code "49") (name "Net-(IC5-PG1)") (class "Default")
      (node (ref "IC5") (pin "33") (pinfunction "PG1_33") (pintype "bidirectional"))
      (node (ref "SL6") (pin "4") (pinfunction "4_4") (pintype "passive"))
    )
    (net (code "50") (name "Net-(IC5-VCAP)") (class "Default")
      (node (ref "C28") (pin "+") (pinfunction "+_+") (pintype "passive"))
      (node (ref "IC5") (pin "6") (pinfunction "VCAP_6") (pintype "power_in"))
    )
    (net (code "51") (name "Net-(IC5-VDDA)") (class "Default")
      (node (ref "C29") (pin "+") (pinfunction "+_+") (pintype "passive"))
      (node (ref "IC5") (pin "12") (pinfunction "VDDA_12") (pintype "power_in"))
      (node (ref "L1") (pin "2") (pinfunction "2_2") (pintype "passive"))
    )
    (net (code "52") (name "Net-(IC6A-QA)") (class "Default")
      (node (ref "IC6") (pin "15") (pinfunction "QA_15") (pintype "tri_state"))
      (node (ref "SL6") (pin "7") (pinfunction "7_7") (pintype "passive"))
    )
    (net (code "53") (name "Net-(IC6A-QB)") (class "Default")
      (node (ref "IC6") (pin "1") (pinfunction "QB_1") (pintype "tri_state"))
      (node (ref "SL6") (pin "8") (pinfunction "8_8") (pintype "passive"))
    )
    (net (code "54") (name "Net-(IC6A-QC)") (class "Default")
      (node (ref "IC6") (pin "2") (pinfunction "QC_2") (pintype "tri_state"))
      (node (ref "SL6") (pin "9") (pinfunction "9_9") (pintype "passive"))
    )
    (net (code "55") (name "Net-(IC6A-QD)") (class "Default")
      (node (ref "IC6") (pin "3") (pinfunction "QD_3") (pintype "tri_state"))
      (node (ref "SL6") (pin "10") (pinfunction "10_10") (pintype "passive"))
    )
    (net (code "56") (name "Net-(IC6A-QE)") (class "Default")
      (node (ref "IC6") (pin "4") (pinfunction "QE_4") (pintype "tri_state"))
      (node (ref "SL6") (pin "11") (pinfunction "11_11") (pintype "passive"))
    )
    (net (code "57") (name "Net-(IC6A-QF)") (class "Default")
      (node (ref "IC6") (pin "5") (pinfunction "QF_5") (pintype "tri_state"))
      (node (ref "SL6") (pin "12") (pinfunction "12_12") (pintype "passive"))
    )
    (net (code "58") (name "Net-(IC6A-QG)") (class "Default")
      (node (ref "IC6") (pin "6") (pinfunction "QG_6") (pintype "tri_state"))
      (node (ref "SL6") (pin "13") (pinfunction "13_13") (pintype "passive"))
    )
    (net (code "59") (name "Net-(IC6A-QH)") (class "Default")
      (node (ref "IC6") (pin "7") (pinfunction "QH_7") (pintype "tri_state"))
      (node (ref "SL6") (pin "14") (pinfunction "14_14") (pintype "passive"))
    )
    (net (code "60") (name "Net-(IC6A-QH*)") (class "Default")
      (node (ref "IC6") (pin "9") (pinfunction "QH*_9") (pintype "tri_state"))
      (node (ref "IC7") (pin "14") (pinfunction "SER_14") (pintype "input"))
    )
    (net (code "61") (name "Net-(IC7A-QA)") (class "Default")
      (node (ref "IC7") (pin "15") (pinfunction "QA_15") (pintype "tri_state"))
      (node (ref "SL3") (pin "4") (pinfunction "4_4") (pintype "passive"))
    )
    (net (code "62") (name "Net-(IC7A-QB)") (class "Default")
      (node (ref "IC7") (pin "1") (pinfunction "QB_1") (pintype "tri_state"))
      (node (ref "SL3") (pin "5") (pinfunction "5_5") (pintype "passive"))
    )
    (net (code "63") (name "Net-(IC7A-QC)") (class "Default")
      (node (ref "IC7") (pin "2") (pinfunction "QC_2") (pintype "tri_state"))
      (node (ref "SL3") (pin "6") (pinfunction "6_6") (pintype "passive"))
    )
    (net (code "64") (name "Net-(IC7A-QD)") (class "Default")
      (node (ref "IC7") (pin "3") (pinfunction "QD_3") (pintype "tri_state"))
      (node (ref "SL3") (pin "7") (pinfunction "7_7") (pintype "passive"))
    )
    (net (code "65") (name "Net-(IC7A-QE)") (class "Default")
      (node (ref "IC7") (pin "4") (pinfunction "QE_4") (pintype "tri_state"))
      (node (ref "SL3") (pin "8") (pinfunction "8_8") (pintype "passive"))
    )
    (net (code "66") (name "Net-(IC7A-QF)") (class "Default")
      (node (ref "IC7") (pin "5") (pinfunction "QF_5") (pintype "tri_state"))
      (node (ref "SL3") (pin "9") (pinfunction "9_9") (pintype "passive"))
    )
    (net (code "67") (name "Net-(IC7A-QG)") (class "Default")
      (node (ref "IC7") (pin "6") (pinfunction "QG_6") (pintype "tri_state"))
      (node (ref "SL3") (pin "10") (pinfunction "10_10") (pintype "passive"))
    )
    (net (code "68") (name "Net-(IC7A-QH)") (class "Default")
      (node (ref "IC7") (pin "7") (pinfunction "QH_7") (pintype "tri_state"))
      (node (ref "SL3") (pin "11") (pinfunction "11_11") (pintype "passive"))
    )
    (net (code "69") (name "Net-(IO2-OSCI)") (class "Default")
      (node (ref "C12") (pin "1") (pinfunction "1_1") (pintype "passive"))
      (node (ref "IO2") (pin "1") (pinfunction "OSCI_1") (pintype "bidirectional"))
      (node (ref "Q3") (pin "2") (pinfunction "2_2") (pintype "passive"))
    )
    (net (code "70") (name "Net-(IO2-OSCO)") (class "Default")
      (node (ref "IO2") (pin "2") (pinfunction "OSCO_2") (pintype "bidirectional"))
      (node (ref "Q3") (pin "1") (pinfunction "1_1") (pintype "passive"))
    )
    (net (code "71") (name "Net-(IO2-VDD)") (class "Default")
      (node (ref "C11") (pin "+") (pinfunction "+_+") (pintype "passive"))
      (node (ref "D7") (pin "C") (pinfunction "C_C") (pintype "passive"))
      (node (ref "IO2") (pin "8") (pinfunction "VDD_8") (pintype "bidirectional"))
      (node (ref "SL11") (pin "1") (pinfunction "S_1") (pintype "passive"))
    )
    (net (code "72") (name "Net-(Q7-PadB)") (class "Default")
      (node (ref "Q7") (pin "B") (pinfunction "B_B") (pintype "passive"))
      (node (ref "Q8") (pin "B") (pinfunction "B_B") (pintype "passive"))
      (node (ref "Q9") (pin "B") (pinfunction "B_B") (pintype "passive"))
      (node (ref "Q9") (pin "C") (pinfunction "C_C") (pintype "passive"))
      (node (ref "R36") (pin "2") (pinfunction "2_2") (pintype "passive"))
    )
    (net (code "73") (name "Net-(Q7-PadE)") (class "Default")
      (node (ref "Q7") (pin "E") (pinfunction "E_E") (pintype "passive"))
      (node (ref "R34") (pin "1") (pinfunction "1_1") (pintype "passive"))
    )
    (net (code "74") (name "Net-(Q8-PadE)") (class "Default")
      (node (ref "Q8") (pin "E") (pinfunction "E_E") (pintype "passive"))
      (node (ref "R35") (pin "1") (pinfunction "1_1") (pintype "passive"))
    )
    (net (code "75") (name "Net-(Q9-PadE)") (class "Default")
      (node (ref "Q9") (pin "E") (pinfunction "E_E") (pintype "passive"))
      (node (ref "R33") (pin "1") (pinfunction "1_1") (pintype "passive"))
    )
    (net (code "76") (name "Net-(R18-PadS)") (class "Default")
      (node (ref "R18") (pin "S") (pinfunction "S_S") (pintype "passive"))
      (node (ref "SL6") (pin "3") (pinfunction "3_3") (pintype "passive"))
    )
    (net (code "77") (name "Net-(R19-Pad1)") (class "Default")
      (node (ref "R19") (pin "1") (pinfunction "1_1") (pintype "passive"))
      (node (ref "SL6") (pin "15") (pinfunction "15_15") (pintype "passive"))
    )
    (net (code "78") (name "Net-(R22-Pad1)") (class "Default")
      (node (ref "R22") (pin "1") (pinfunction "1_1") (pintype "passive"))
      (node (ref "SL7") (pin "2") (pinfunction "2_2") (pintype "passive"))
    )
    (net (code "79") (name "Net-(R23-Pad1)") (class "Default")
      (node (ref "R23") (pin "1") (pinfunction "1_1") (pintype "passive"))
      (node (ref "SL7") (pin "5") (pinfunction "5_5") (pintype "passive"))
    )
    (net (code "80") (name "Net-(R29-Pad1)") (class "Default")
      (node (ref "R29") (pin "1") (pinfunction "1_1") (pintype "passive"))
      (node (ref "SL5") (pin "7") (pinfunction "7_7") (pintype "passive"))
    )
    (net (code "81") (name "Net-(R30-Pad1)") (class "Default")
      (node (ref "R30") (pin "1") (pinfunction "1_1") (pintype "passive"))
      (node (ref "SL5") (pin "5") (pinfunction "5_5") (pintype "passive"))
    )
    (net (code "82") (name "Net-(R31-Pad1)") (class "Default")
      (node (ref "R31") (pin "1") (pinfunction "1_1") (pintype "passive"))
      (node (ref "SL5") (pin "3") (pinfunction "3_3") (pintype "passive"))
    )
    (net (code "83") (name "Net-(R32-Pad1)") (class "Default")
      (node (ref "R32") (pin "1") (pinfunction "1_1") (pintype "passive"))
      (node (ref "SL5") (pin "1") (pinfunction "1_1") (pintype "passive"))
    )
    (net (code "84") (name "OSC1KHZ_OUT") (class "Default")
      (node (ref "C1") (pin "2") (pinfunction "2_2") (pintype "passive"))
      (node (ref "IC1") (pin "1") (pinfunction "OUT_1") (pintype "output"))
      (node (ref "IC3") (pin "10") (pinfunction "+IN_10") (pintype "input"))
      (node (ref "IC3") (pin "3") (pinfunction "+IN_3") (pintype "input"))
      (node (ref "R3") (pin "1") (pinfunction "1_1") (pintype "passive"))
      (node (ref "R5") (pin "1") (pinfunction "1_1") (pintype "passive"))
    )
    (net (code "85") (name "RCK0") (class "Default")
      (node (ref "IC5") (pin "26") (pinfunction "PC3/TIM1_CH3_26") (pintype "bidirectional"))
      (node (ref "IC6") (pin "12") (pinfunction "RCK_12") (pintype "input"))
    )
    (net (code "86") (name "RCK1") (class "Default")
      (node (ref "IC5") (pin "31") (pinfunction "PC7/SPI_MISO_31") (pintype "bidirectional"))
      (node (ref "IC7") (pin "12") (pinfunction "RCK_12") (pintype "input"))
    )
    (net (code "87") (name "SCK") (class "Default")
      (node (ref "IC5") (pin "27") (pinfunction "PC5/SPI_SCK_27") (pintype "bidirectional"))
      (node (ref "IC6") (pin "11") (pinfunction "SCK_11") (pintype "input"))
      (node (ref "IC7") (pin "11") (pinfunction "SCK_11") (pintype "input"))
    )
    (net (code "88") (name "SCL") (class "Default")
      (node (ref "IC5") (pin "30") (pinfunction "PC6/SPI_MOSI_30") (pintype "bidirectional"))
      (node (ref "IC6") (pin "10") (pinfunction "SCL_10") (pintype "input"))
      (node (ref "IC7") (pin "10") (pinfunction "SCL_10") (pintype "input"))
    )
    (net (code "89") (name "SER") (class "Default")
      (node (ref "IC5") (pin "25") (pinfunction "PC2/TIM1_CH2_25") (pintype "bidirectional"))
      (node (ref "IC6") (pin "14") (pinfunction "SER_14") (pintype "input"))
    )
    (net (code "90") (name "TL1") (class "Default")
      (node (ref "C13") (pin "1") (pinfunction "1_1") (pintype "passive"))
      (node (ref "IC5") (pin "9") (pinfunction "PA4_9") (pintype "bidirectional"))
      (node (ref "R20") (pin "1") (pinfunction "1_1") (pintype "passive"))
      (node (ref "SL8") (pin "1") (pinfunction "S_1") (pintype "passive"))
    )
    (net (code "91") (name "TL2") (class "Default")
      (node (ref "C23") (pin "1") (pinfunction "1_1") (pintype "passive"))
      (node (ref "IC5") (pin "10") (pinfunction "PA5_10") (pintype "bidirectional"))
      (node (ref "R21") (pin "1") (pinfunction "1_1") (pintype "passive"))
      (node (ref "SL9") (pin "1") (pinfunction "S_1") (pintype "passive"))
    )
    (net (code "92") (name "TL3") (class "Default")
      (node (ref "C24") (pin "1") (pinfunction "1_1") (pintype "passive"))
      (node (ref "IC5") (pin "11") (pinfunction "PA6_11") (pintype "bidirectional"))
      (node (ref "R24") (pin "1") (pinfunction "1_1") (pintype "passive"))
      (node (ref "SL10") (pin "1") (pinfunction "S_1") (pintype "passive"))
    )
    (net (code "93") (name "TL4") (class "Default")
      (node (ref "C32") (pin "1") (pinfunction "1_1") (pintype "passive"))
      (node (ref "IC5") (pin "44") (pinfunction "PD7/TLI[TIM1_CH4]_44") (pintype "bidirectional"))
      (node (ref "R27") (pin "1") (pinfunction "1_1") (pintype "passive"))
      (node (ref "SL2") (pin "1") (pinfunction "S_1") (pintype "passive"))
    )
    (net (code "94") (name "VDD") (class "Default")
      (node (ref "C20") (pin "+") (pinfunction "+_+") (pintype "passive"))
      (node (ref "C21") (pin "+") (pinfunction "+_+") (pintype "passive"))
      (node (ref "C30") (pin "2") (pinfunction "2_2") (pintype "passive"))
      (node (ref "D7") (pin "A") (pinfunction "A_A") (pintype "passive"))
      (node (ref "IC1") (pin "8") (pinfunction "V+_8") (pintype "power_in"))
      (node (ref "IC2") (pin "16") (pinfunction "VCC_16") (pintype "power_in"))
      (node (ref "IC3") (pin "4") (pinfunction "V+_4") (pintype "power_in"))
      (node (ref "IC5") (pin "29") (pinfunction "VDDIO_2_29") (pintype "power_in"))
      (node (ref "IC5") (pin "7") (pinfunction "VDD_7") (pintype "power_in"))
      (node (ref "IC5") (pin "8") (pinfunction "VDDIO_1_8") (pintype "power_in"))
      (node (ref "IC6") (pin "16") (pinfunction "VCC_16") (pintype "power_in"))
      (node (ref "IC7") (pin "16") (pinfunction "VCC_16") (pintype "power_in"))
      (node (ref "L1") (pin "1") (pinfunction "1_1") (pintype "passive"))
      (node (ref "R16") (pin "2") (pinfunction "2_2") (pintype "passive"))
      (node (ref "R17") (pin "2") (pinfunction "2_2") (pintype "passive"))
      (node (ref "R18") (pin "E") (pinfunction "E_E") (pintype "passive"))
      (node (ref "R19") (pin "2") (pinfunction "2_2") (pintype "passive"))
      (node (ref "R20") (pin "2") (pinfunction "2_2") (pintype "passive"))
      (node (ref "R21") (pin "2") (pinfunction "2_2") (pintype "passive"))
      (node (ref "R24") (pin "2") (pinfunction "2_2") (pintype "passive"))
      (node (ref "R25") (pin "2") (pinfunction "2_2") (pintype "passive"))
      (node (ref "R26") (pin "1") (pinfunction "1_1") (pintype "passive"))
      (node (ref "R27") (pin "2") (pinfunction "2_2") (pintype "passive"))
      (node (ref "R33") (pin "2") (pinfunction "2_2") (pintype "passive"))
      (node (ref "R34") (pin "2") (pinfunction "2_2") (pintype "passive"))
      (node (ref "R35") (pin "2") (pinfunction "2_2") (pintype "passive"))
      (node (ref "R37") (pin "2") (pinfunction "2_2") (pintype "passive"))
      (node (ref "SL3") (pin "1") (pinfunction "1_1") (pintype "passive"))
      (node (ref "SL4") (pin "1") (pinfunction "1_1") (pintype "passive"))
      (node (ref "SL5") (pin "8") (pinfunction "8_8") (pintype "passive"))
      (node (ref "SL6") (pin "2") (pinfunction "2_2") (pintype "passive"))
      (node (ref "X2") (pin "1") (pinfunction "KL_1") (pintype "passive"))
    )
    (net (code "95") (name "ZERO_SENS") (class "Default")
      (node (ref "IC5") (pin "24") (pinfunction "PC1/TIM1_CH1/UART2_CK_24") (pintype "bidirectional"))
      (node (ref "SL3") (pin "3") (pinfunction "3_3") (pintype "passive"))
    )
    (net (code "96") (name "unconnected-(IC2A-R2OUT-Pad9)") (class "Default")
      (node (ref "IC2") (pin "9") (pinfunction "R2OUT_9") (pintype "output"))
    )
    (net (code "97") (name "unconnected-(IC2A-T2OUT-Pad7)") (class "Default")
      (node (ref "IC2") (pin "7") (pinfunction "T2OUT_7") (pintype "output"))
    )
    (net (code "98") (name "unconnected-(IC5-PD0{slash}TIM3_CH2[TIM1_BKIN][CLK_CCO]-Pad37)") (class "Default")
      (node (ref "IC5") (pin "37") (pinfunction "PD0/TIM3_CH2[TIM1_BKIN][CLK_CCO]_37") (pintype "bidirectional"))
    )
    (net (code "99") (name "unconnected-(IC5-PD2{slash}TIM3_CH1[TIM2_CH3]-Pad39)") (class "Default")
      (node (ref "IC5") (pin "39") (pinfunction "PD2/TIM3_CH1[TIM2_CH3]_39") (pintype "bidirectional"))
    )
    (net (code "100") (name "unconnected-(IC5-PD3{slash}TIM2_CH2[ADC_ETR]-Pad40)") (class "Default")
      (node (ref "IC5") (pin "40") (pinfunction "PD3/TIM2_CH2[ADC_ETR]_40") (pintype "bidirectional"))
    )
    (net (code "101") (name "unconnected-(IC5-PD4{slash}TIM2_CH1[BEEP]-Pad41)") (class "Default")
      (node (ref "IC5") (pin "41") (pinfunction "PD4/TIM2_CH1[BEEP]_41") (pintype "bidirectional"))
    )
    (net (code "102") (name "unconnected-(IC5-PE5{slash}SPI_NSS-Pad23)") (class "Default")
      (node (ref "IC5") (pin "23") (pinfunction "PE5/SPI_NSS_23") (pintype "bidirectional"))
    )
    (net (code "103") (name "unconnected-(IC5-PE6{slash}AIN9-Pad22)") (class "Default")
      (node (ref "IC5") (pin "22") (pinfunction "PE6/AIN9_22") (pintype "bidirectional"))
    )
    (net (code "104") (name "unconnected-(IC7A-QH*-Pad9)") (class "Default")
      (node (ref "IC7") (pin "9") (pinfunction "QH*_9") (pintype "tri_state"))
    )
    (net (code "105") (name "unconnected-(IO2-CLKOUT-Pad7)") (class "Default")
      (node (ref "IO2") (pin "7") (pinfunction "CLKOUT_7") (pintype "bidirectional"))
    )
    (net (code "106") (name "unconnected-(X1A-F-Pad1)") (class "Default")
      (node (ref "X1") (pin "1") (pinfunction "F_1") (pintype "passive"))
    )
    (net (code "107") (name "unconnected-(X1D-F-Pad4)") (class "Default")
      (node (ref "X1") (pin "4") (pinfunction "F_4") (pintype "passive"))
    )
    (net (code "108") (name "unconnected-(X1F-F-Pad6)") (class "Default")
      (node (ref "X1") (pin "6") (pinfunction "F_6") (pintype "passive"))
    )
    (net (code "109") (name "unconnected-(X1G-F-Pad7)") (class "Default")
      (node (ref "X1") (pin "7") (pinfunction "F_7") (pintype "passive"))
    )
    (net (code "110") (name "unconnected-(X1H-F-Pad8)") (class "Default")
      (node (ref "X1") (pin "8") (pinfunction "F_8") (pintype "passive"))
    )
    (net (code "111") (name "unconnected-(X1I-F-Pad9)") (class "Default")
      (node (ref "X1") (pin "9") (pinfunction "F_9") (pintype "passive"))
    )
  )
)
